# WIFI_Bluetooth.net
KiCad netlist of a schematic drawn in Altium Designer
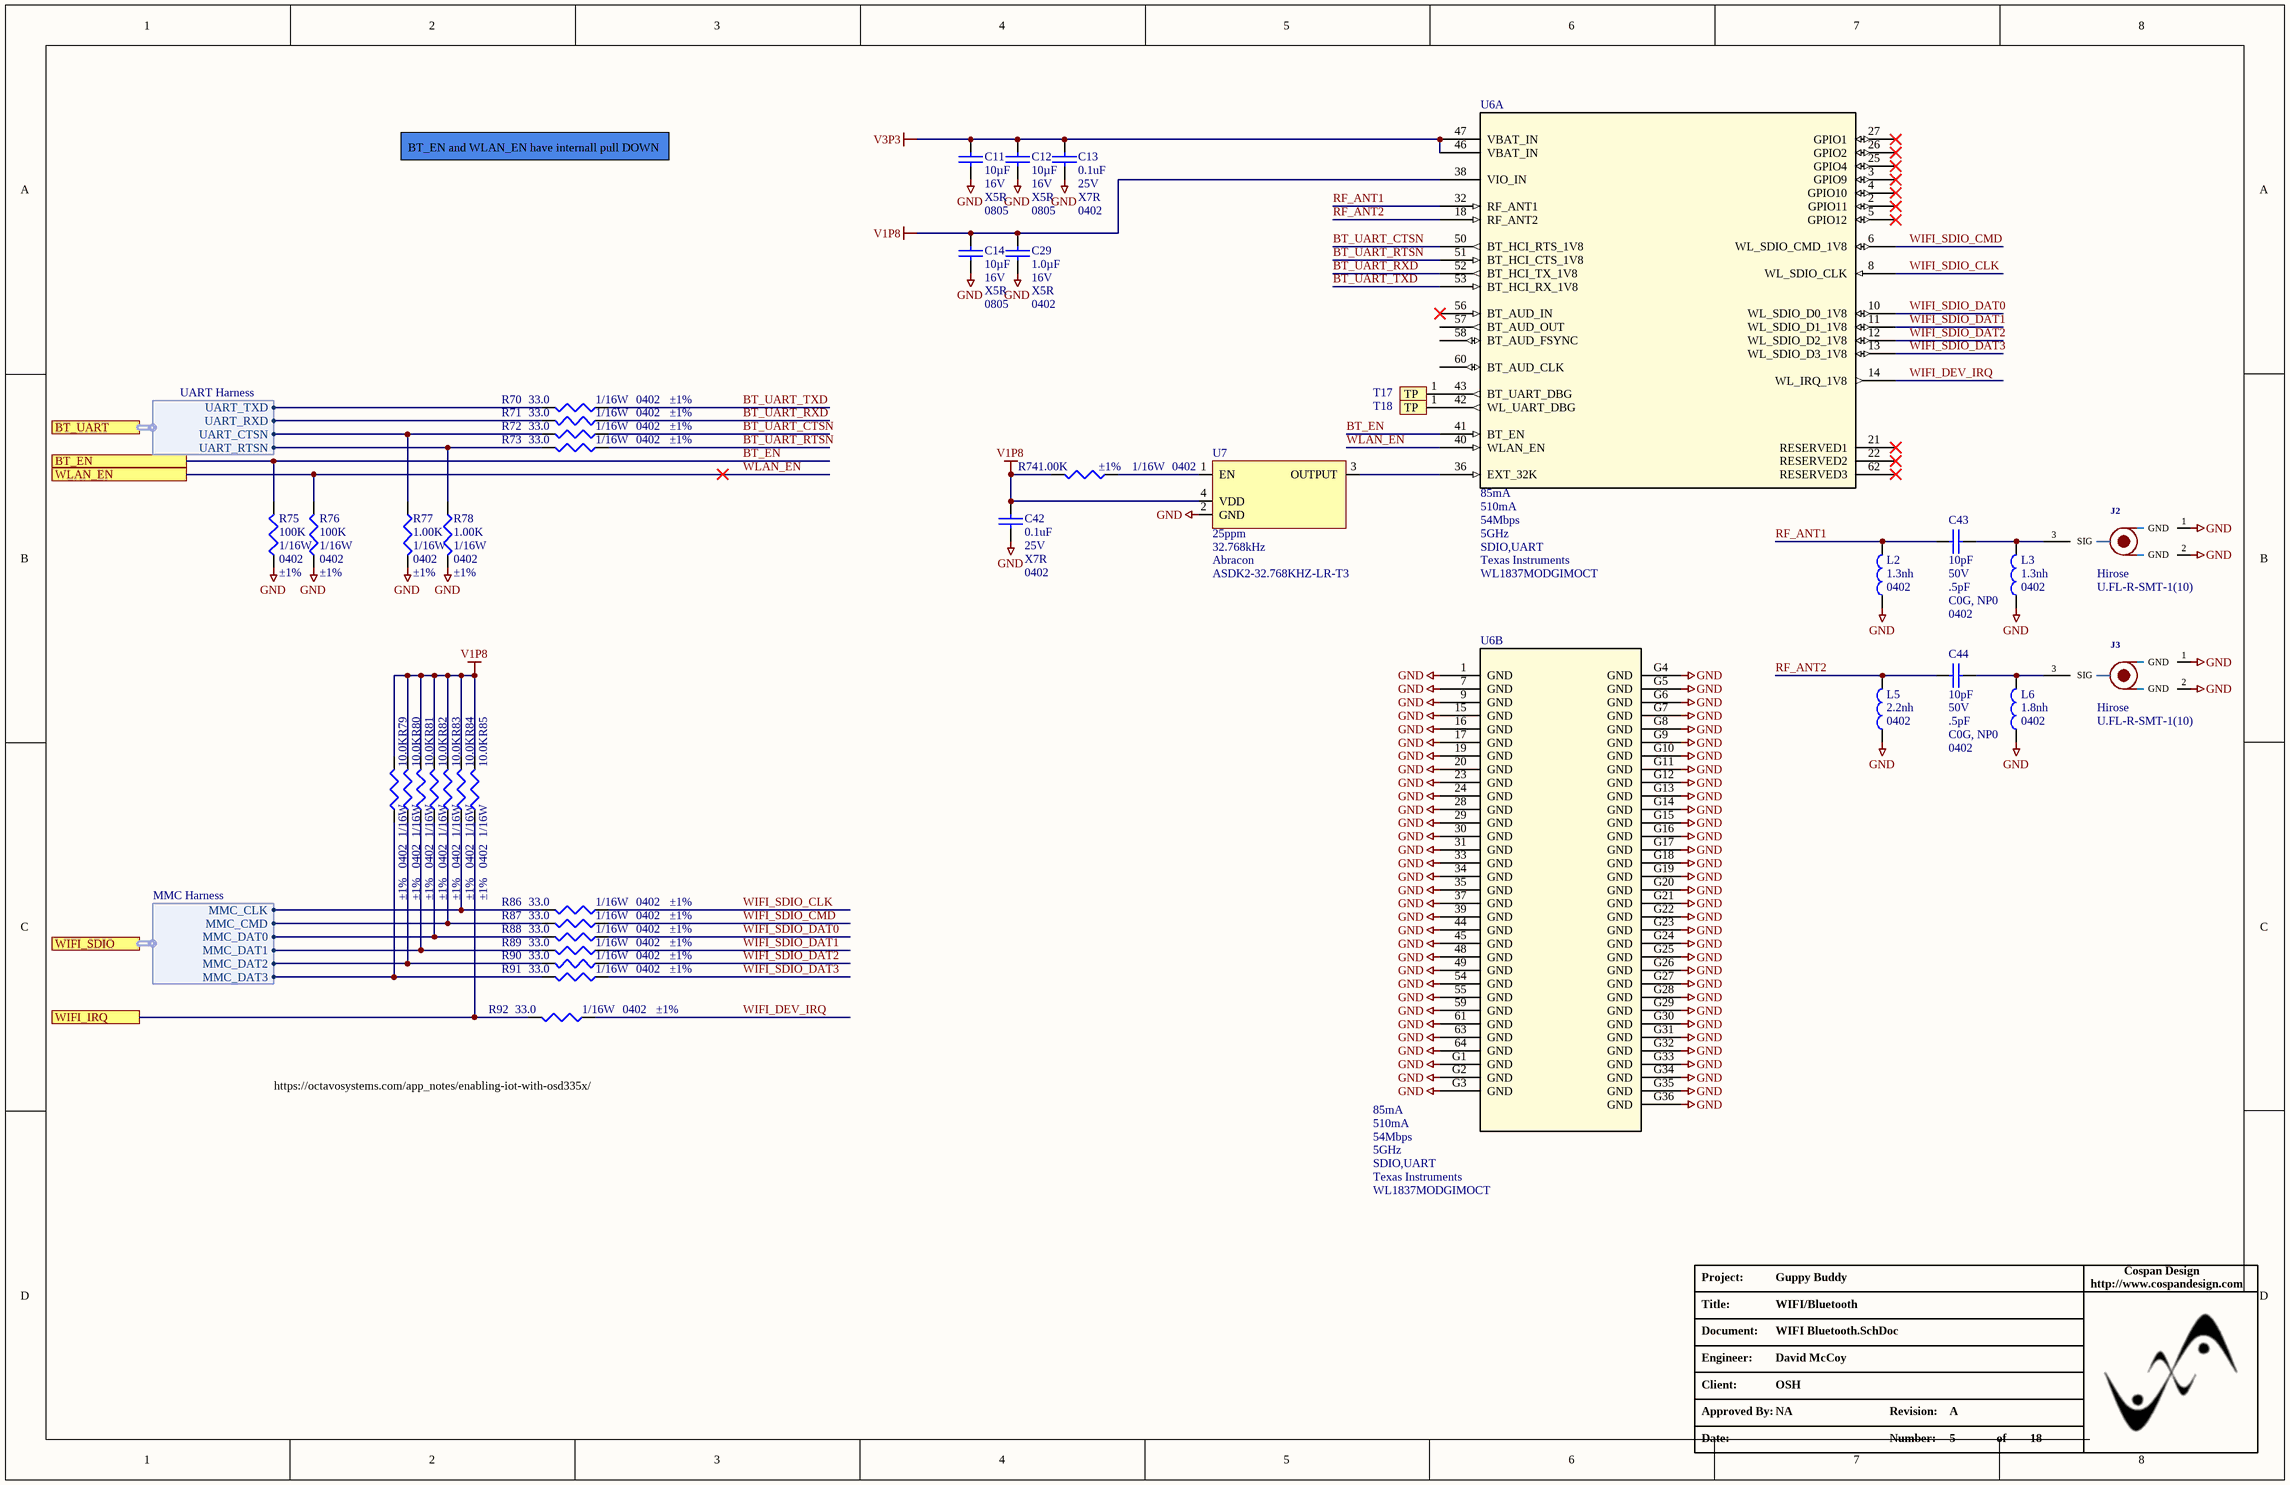
[diagram p0: WIFI Bluetooth.SchDoc]

(export (version "E")
  (design (tool "Eeschema 10.0.6"))
  (components
    (comp (ref "C11")
      (value "10µF")
      (footprint "C_ERA-0805")
      (description "CAP CER 10uF 16V X5R 20% 0805")
      (fields
        (field (name "MANUFACTURER") "Taiyo Yuden")
        (field (name "MANUFACTURER PART NUMBER") "EMK212BJ106KG-T")
        (field (name "CAPACITANCE") "10µF")
        (field (name "VOLTAGE - RATED") "16V")
        (field (name "TEMPERATURE COEFFICIENT") "X5R")
        (field (name "PACKAGE / CASE") "0805")
      )
      (libsource (lib "Main Library") (part "C_0805_10UF_16V"))
    )
    (comp (ref "C12")
      (value "10µF")
      (footprint "C_ERA-0805")
      (description "CAP CER 10uF 16V X5R 20% 0805")
      (fields
        (field (name "MANUFACTURER") "Taiyo Yuden")
        (field (name "MANUFACTURER PART NUMBER") "EMK212BJ106KG-T")
        (field (name "CAPACITANCE") "10µF")
        (field (name "VOLTAGE - RATED") "16V")
        (field (name "TEMPERATURE COEFFICIENT") "X5R")
        (field (name "PACKAGE / CASE") "0805")
      )
      (libsource (lib "Main Library") (part "C_0805_10UF_16V"))
    )
    (comp (ref "C13")
      (value "C_0402_0.1UF_25V")
      (footprint "C_0402")
      (description "CAP CER 0.1UF 25V X6S 0402")
      (fields
        (field (name "TOLERANCE") "10%")
        (field (name "CAPACITANCE") "0.1uF")
        (field (name "VOLTAGE - RATED") "25V")
        (field (name "TEMPERATURE COEFFICIENT") "X7R")
        (field (name "PACKAGE / CASE") "0402")
      )
      (libsource (lib "Cospan Design") (part "C_0402_0.1UF_25V"))
    )
    (comp (ref "C14")
      (value "10µF")
      (footprint "C_ERA-0805")
      (description "CAP CER 10uF 16V X5R 20% 0805")
      (fields
        (field (name "MANUFACTURER") "Taiyo Yuden")
        (field (name "MANUFACTURER PART NUMBER") "EMK212BJ106KG-T")
        (field (name "CAPACITANCE") "10µF")
        (field (name "VOLTAGE - RATED") "16V")
        (field (name "TEMPERATURE COEFFICIENT") "X5R")
        (field (name "PACKAGE / CASE") "0805")
      )
      (libsource (lib "Main Library") (part "C_0805_10UF_16V"))
    )
    (comp (ref "C29")
      (value "1.0uF")
      (footprint "C_0402")
      (description "CAP CER 1.0UF 16V X5R 0402")
      (fields
        (field (name "TOLERANCE") "10%")
        (field (name "CAPACITANCE") "1.0µF")
        (field (name "VOLTAGE - RATED") "16V")
        (field (name "TEMPERATURE COEFFICIENT") "X5R")
        (field (name "PACKAGE / CASE") "0402")
        (field (name "VOLTAGE") "16V")
      )
      (libsource (lib "Main LibraryX") (part "C_0402_1.0UF_16V"))
    )
    (comp (ref "C42")
      (value "C_0402_0.1UF_25V")
      (footprint "C_0402")
      (description "CAP CER 0.1UF 25V X6S 0402")
      (fields
        (field (name "TOLERANCE") "10%")
        (field (name "CAPACITANCE") "0.1uF")
        (field (name "VOLTAGE - RATED") "25V")
        (field (name "TEMPERATURE COEFFICIENT") "X7R")
        (field (name "PACKAGE / CASE") "0402")
      )
      (libsource (lib "Cospan Design") (part "C_0402_0.1UF_25V"))
    )
    (comp (ref "C43")
      (value "10pF")
      (footprint "C_0402")
      (description "CAP CER 10PF 50V NP0 0402")
      (fields
        (field (name "MANUFACTURER") "Taiyo Yuden")
        (field (name "MANUFACTURER PART NUMBER") "UMK105CG100DV-F")
        (field (name "CAPACITANCE") "10pF")
        (field (name "VOLTAGE - RATED") "50V")
        (field (name "TOLERANCE") ".5pF")
        (field (name "TEMPERATURE COEFFICIENT") "C0G, NP0")
        (field (name "PACKAGE / CASE") "0402")
      )
      (libsource (lib "Main Library") (part "C_0402_10PF_50V"))
    )
    (comp (ref "C44")
      (value "10pF")
      (footprint "C_0402")
      (description "CAP CER 10PF 50V NP0 0402")
      (fields
        (field (name "MANUFACTURER") "Taiyo Yuden")
        (field (name "MANUFACTURER PART NUMBER") "UMK105CG100DV-F")
        (field (name "CAPACITANCE") "10pF")
        (field (name "VOLTAGE - RATED") "50V")
        (field (name "TOLERANCE") ".5pF")
        (field (name "TEMPERATURE COEFFICIENT") "C0G, NP0")
        (field (name "PACKAGE / CASE") "0402")
      )
      (libsource (lib "Main Library") (part "C_0402_10PF_50V"))
    )
    (comp (ref "J2")
      (value "U.FL-R-SMT-1(10)")
      (footprint "U.FL-R-SMT-1")
      (description "CONN UMC JACK STR 50 OHM SMD")
      (fields
        (field (name "MANUFACTURER 1") "Hirose")
        (field (name "MANUFACTURER PART NUMBER 1") "U.FL-R-SMT-1(10)")
        (field (name "LIBRARYNAME") "GHI-Connectors")
      )
      (libsource (lib "Cospan Design") (part "J_U.FL-R-SMT-1"))
    )
    (comp (ref "J3")
      (value "U.FL-R-SMT-1(10)")
      (footprint "U.FL-R-SMT-1")
      (description "CONN UMC JACK STR 50 OHM SMD")
      (fields
        (field (name "MANUFACTURER 1") "Hirose")
        (field (name "MANUFACTURER PART NUMBER 1") "U.FL-R-SMT-1(10)")
        (field (name "LIBRARYNAME") "GHI-Connectors")
      )
      (libsource (lib "Cospan Design") (part "J_U.FL-R-SMT-1"))
    )
    (comp (ref "L2")
      (value "L_0402_1.3nH")
      (footprint "R_0402")
      (description "FIXED IND 1.3NH 1A 90 MOHM")
      (fields
        (field (name "TOLERANCE") "5%")
        (field (name "INDUCTANCE") "1.3nh")
        (field (name "CASE CODE (IMPERIAL)") "0402")
      )
      (libsource (lib "Cospan Design") (part "L_0402_1.3nH"))
    )
    (comp (ref "L3")
      (value "L_0402_1.3nH")
      (footprint "R_0402")
      (description "FIXED IND 1.3NH 1A 90 MOHM")
      (fields
        (field (name "TOLERANCE") "5%")
        (field (name "INDUCTANCE") "1.3nh")
        (field (name "CASE CODE (IMPERIAL)") "0402")
      )
      (libsource (lib "Cospan Design") (part "L_0402_1.3nH"))
    )
    (comp (ref "L5")
      (value "L_0402_2.2nH")
      (footprint "R_0402")
      (description "FIXED IND 2.2NH 950MA 150 MOHM")
      (fields (field (name "INDUCTANCE") "2.2nh") (field (name "CASE CODE (IMPERIAL)") "0402"))
      (libsource (lib "Cospan Design") (part "L_0402_2.2nH"))
    )
    (comp (ref "L6")
      (value "L_0402_1.8nH")
      (footprint "R_0402")
      (description "FIXED IND 1.8NH 950MA 100 MOHM")
      (fields (field (name "INDUCTANCE") "1.8nh") (field (name "CASE CODE (IMPERIAL)") "0402"))
      (libsource (lib "Cospan Design") (part "L_0402_1.8nH"))
    )
    (comp (ref "R70")
      (value "R_0402_33")
      (footprint "R_0402")
      (description "RES 33.0 OHM 1/16W 1% 0402 SMD")
      (fields
        (field (name "MANUFACTURER") "Yageo")
        (field (name "MANUFACTURER PART NUMBER") "RC0402FR-0733RL")
        (field (name "RESISTANCE IN OHMS") "33.0")
        (field (name "POWER (WATTS)") "1/16W")
        (field (name "CASE") "0402")
        (field (name "TOLERANCE") "±1%")
      )
      (libsource (lib "Main Library") (part "R_0402_33"))
    )
    (comp (ref "R71")
      (value "R_0402_33")
      (footprint "R_0402")
      (description "RES 33.0 OHM 1/16W 1% 0402 SMD")
      (fields
        (field (name "MANUFACTURER") "Yageo")
        (field (name "MANUFACTURER PART NUMBER") "RC0402FR-0733RL")
        (field (name "RESISTANCE IN OHMS") "33.0")
        (field (name "POWER (WATTS)") "1/16W")
        (field (name "CASE") "0402")
        (field (name "TOLERANCE") "±1%")
      )
      (libsource (lib "Main Library") (part "R_0402_33"))
    )
    (comp (ref "R72")
      (value "R_0402_33")
      (footprint "R_0402")
      (description "RES 33.0 OHM 1/16W 1% 0402 SMD")
      (fields
        (field (name "MANUFACTURER") "Yageo")
        (field (name "MANUFACTURER PART NUMBER") "RC0402FR-0733RL")
        (field (name "RESISTANCE IN OHMS") "33.0")
        (field (name "POWER (WATTS)") "1/16W")
        (field (name "CASE") "0402")
        (field (name "TOLERANCE") "±1%")
      )
      (libsource (lib "Main Library") (part "R_0402_33"))
    )
    (comp (ref "R73")
      (value "R_0402_33")
      (footprint "R_0402")
      (description "RES 33.0 OHM 1/16W 1% 0402 SMD")
      (fields
        (field (name "MANUFACTURER") "Yageo")
        (field (name "MANUFACTURER PART NUMBER") "RC0402FR-0733RL")
        (field (name "RESISTANCE IN OHMS") "33.0")
        (field (name "POWER (WATTS)") "1/16W")
        (field (name "CASE") "0402")
        (field (name "TOLERANCE") "±1%")
      )
      (libsource (lib "Main Library") (part "R_0402_33"))
    )
    (comp (ref "R74")
      (value "1.0k Ohms")
      (footprint "R_0402")
      (description "RES 1.00K OHM 1/16W 1% 0402 SMD")
      (fields
        (field (name "MANUFACTURER") "Yageo")
        (field (name "MANUFACTURER PART NUMBER") "RC0402FR-071KL")
        (field (name "RESISTANCE IN OHMS") "1.00K")
        (field (name "POWER (WATTS)") "1/16W")
        (field (name "CASE") "0402")
        (field (name "TOLERANCE") "±1%")
      )
      (libsource (lib "Main Library") (part "R_0402_1.0K"))
    )
    (comp (ref "R75")
      (value "R_0402_100.0K")
      (footprint "R_0402")
      (description "RES 100K OHM 1/16W 1% 0402 SMD")
      (fields
        (field (name "MANUFACTURER") "Stackpole Electronics Inc")
        (field (name "MANUFACTURER PART NUMBER") "RMCF0402FT100K")
        (field (name "RESISTANCE IN OHMS") "100K")
        (field (name "POWER (WATTS)") "1/16W")
        (field (name "CASE") "0402")
        (field (name "TOLERANCE") "±1%")
      )
      (libsource (lib "Main Library") (part "R_0402_100.0K"))
    )
    (comp (ref "R76")
      (value "R_0402_100.0K")
      (footprint "R_0402")
      (description "RES 100K OHM 1/16W 1% 0402 SMD")
      (fields
        (field (name "MANUFACTURER") "Stackpole Electronics Inc")
        (field (name "MANUFACTURER PART NUMBER") "RMCF0402FT100K")
        (field (name "RESISTANCE IN OHMS") "100K")
        (field (name "POWER (WATTS)") "1/16W")
        (field (name "CASE") "0402")
        (field (name "TOLERANCE") "±1%")
      )
      (libsource (lib "Main Library") (part "R_0402_100.0K"))
    )
    (comp (ref "R77")
      (value "1.0k Ohms")
      (footprint "R_0402")
      (description "RES 1.00K OHM 1/16W 1% 0402 SMD")
      (fields
        (field (name "MANUFACTURER") "Yageo")
        (field (name "MANUFACTURER PART NUMBER") "RC0402FR-071KL")
        (field (name "RESISTANCE IN OHMS") "1.00K")
        (field (name "POWER (WATTS)") "1/16W")
        (field (name "CASE") "0402")
        (field (name "TOLERANCE") "±1%")
      )
      (libsource (lib "Main Library") (part "R_0402_1.0K"))
    )
    (comp (ref "R78")
      (value "1.0k Ohms")
      (footprint "R_0402")
      (description "RES 1.00K OHM 1/16W 1% 0402 SMD")
      (fields
        (field (name "MANUFACTURER") "Yageo")
        (field (name "MANUFACTURER PART NUMBER") "RC0402FR-071KL")
        (field (name "RESISTANCE IN OHMS") "1.00K")
        (field (name "POWER (WATTS)") "1/16W")
        (field (name "CASE") "0402")
        (field (name "TOLERANCE") "±1%")
      )
      (libsource (lib "Main Library") (part "R_0402_1.0K"))
    )
    (comp (ref "R79")
      (value "R_0402_10.0K")
      (footprint "R_0402")
      (description "RES 10.0K OHM 1/16W 1% 0402 SMD")
      (fields
        (field (name "MANUFACTURER") "Stackpole Electronics Inc")
        (field (name "MANUFACTURER PART NUMBER") "RMCF0402FT10K0")
        (field (name "RESISTANCE IN OHMS") "10.0K")
        (field (name "POWER (WATTS)") "1/16W")
        (field (name "CASE") "0402")
        (field (name "TOLERANCE") "±1%")
      )
      (libsource (lib "Cospan Design") (part "R_0402_10.0K"))
    )
    (comp (ref "R80")
      (value "R_0402_10.0K")
      (footprint "R_0402")
      (description "RES 10.0K OHM 1/16W 1% 0402 SMD")
      (fields
        (field (name "MANUFACTURER") "Stackpole Electronics Inc")
        (field (name "MANUFACTURER PART NUMBER") "RMCF0402FT10K0")
        (field (name "RESISTANCE IN OHMS") "10.0K")
        (field (name "POWER (WATTS)") "1/16W")
        (field (name "CASE") "0402")
        (field (name "TOLERANCE") "±1%")
      )
      (libsource (lib "Cospan Design") (part "R_0402_10.0K"))
    )
    (comp (ref "R81")
      (value "R_0402_10.0K")
      (footprint "R_0402")
      (description "RES 10.0K OHM 1/16W 1% 0402 SMD")
      (fields
        (field (name "MANUFACTURER") "Stackpole Electronics Inc")
        (field (name "MANUFACTURER PART NUMBER") "RMCF0402FT10K0")
        (field (name "RESISTANCE IN OHMS") "10.0K")
        (field (name "POWER (WATTS)") "1/16W")
        (field (name "CASE") "0402")
        (field (name "TOLERANCE") "±1%")
      )
      (libsource (lib "Cospan Design") (part "R_0402_10.0K"))
    )
    (comp (ref "R82")
      (value "R_0402_10.0K")
      (footprint "R_0402")
      (description "RES 10.0K OHM 1/16W 1% 0402 SMD")
      (fields
        (field (name "MANUFACTURER") "Stackpole Electronics Inc")
        (field (name "MANUFACTURER PART NUMBER") "RMCF0402FT10K0")
        (field (name "RESISTANCE IN OHMS") "10.0K")
        (field (name "POWER (WATTS)") "1/16W")
        (field (name "CASE") "0402")
        (field (name "TOLERANCE") "±1%")
      )
      (libsource (lib "Cospan Design") (part "R_0402_10.0K"))
    )
    (comp (ref "R83")
      (value "R_0402_10.0K")
      (footprint "R_0402")
      (description "RES 10.0K OHM 1/16W 1% 0402 SMD")
      (fields
        (field (name "MANUFACTURER") "Stackpole Electronics Inc")
        (field (name "MANUFACTURER PART NUMBER") "RMCF0402FT10K0")
        (field (name "RESISTANCE IN OHMS") "10.0K")
        (field (name "POWER (WATTS)") "1/16W")
        (field (name "CASE") "0402")
        (field (name "TOLERANCE") "±1%")
      )
      (libsource (lib "Cospan Design") (part "R_0402_10.0K"))
    )
    (comp (ref "R84")
      (value "R_0402_10.0K")
      (footprint "R_0402")
      (description "RES 10.0K OHM 1/16W 1% 0402 SMD")
      (fields
        (field (name "MANUFACTURER") "Stackpole Electronics Inc")
        (field (name "MANUFACTURER PART NUMBER") "RMCF0402FT10K0")
        (field (name "RESISTANCE IN OHMS") "10.0K")
        (field (name "POWER (WATTS)") "1/16W")
        (field (name "CASE") "0402")
        (field (name "TOLERANCE") "±1%")
      )
      (libsource (lib "Cospan Design") (part "R_0402_10.0K"))
    )
    (comp (ref "R85")
      (value "R_0402_10.0K")
      (footprint "R_0402")
      (description "RES 10.0K OHM 1/16W 1% 0402 SMD")
      (fields
        (field (name "MANUFACTURER") "Stackpole Electronics Inc")
        (field (name "MANUFACTURER PART NUMBER") "RMCF0402FT10K0")
        (field (name "RESISTANCE IN OHMS") "10.0K")
        (field (name "POWER (WATTS)") "1/16W")
        (field (name "CASE") "0402")
        (field (name "TOLERANCE") "±1%")
      )
      (libsource (lib "Cospan Design") (part "R_0402_10.0K"))
    )
    (comp (ref "R86")
      (value "R_0402_33")
      (footprint "R_0402")
      (description "RES 33.0 OHM 1/16W 1% 0402 SMD")
      (fields
        (field (name "MANUFACTURER") "Yageo")
        (field (name "MANUFACTURER PART NUMBER") "RC0402FR-0733RL")
        (field (name "RESISTANCE IN OHMS") "33.0")
        (field (name "POWER (WATTS)") "1/16W")
        (field (name "CASE") "0402")
        (field (name "TOLERANCE") "±1%")
      )
      (libsource (lib "Main Library") (part "R_0402_33"))
    )
    (comp (ref "R87")
      (value "R_0402_33")
      (footprint "R_0402")
      (description "RES 33.0 OHM 1/16W 1% 0402 SMD")
      (fields
        (field (name "MANUFACTURER") "Yageo")
        (field (name "MANUFACTURER PART NUMBER") "RC0402FR-0733RL")
        (field (name "RESISTANCE IN OHMS") "33.0")
        (field (name "POWER (WATTS)") "1/16W")
        (field (name "CASE") "0402")
        (field (name "TOLERANCE") "±1%")
      )
      (libsource (lib "Main Library") (part "R_0402_33"))
    )
    (comp (ref "R88")
      (value "R_0402_33")
      (footprint "R_0402")
      (description "RES 33.0 OHM 1/16W 1% 0402 SMD")
      (fields
        (field (name "MANUFACTURER") "Yageo")
        (field (name "MANUFACTURER PART NUMBER") "RC0402FR-0733RL")
        (field (name "RESISTANCE IN OHMS") "33.0")
        (field (name "POWER (WATTS)") "1/16W")
        (field (name "CASE") "0402")
        (field (name "TOLERANCE") "±1%")
      )
      (libsource (lib "Main Library") (part "R_0402_33"))
    )
    (comp (ref "R89")
      (value "R_0402_33")
      (footprint "R_0402")
      (description "RES 33.0 OHM 1/16W 1% 0402 SMD")
      (fields
        (field (name "MANUFACTURER") "Yageo")
        (field (name "MANUFACTURER PART NUMBER") "RC0402FR-0733RL")
        (field (name "RESISTANCE IN OHMS") "33.0")
        (field (name "POWER (WATTS)") "1/16W")
        (field (name "CASE") "0402")
        (field (name "TOLERANCE") "±1%")
      )
      (libsource (lib "Main Library") (part "R_0402_33"))
    )
    (comp (ref "R90")
      (value "R_0402_33")
      (footprint "R_0402")
      (description "RES 33.0 OHM 1/16W 1% 0402 SMD")
      (fields
        (field (name "MANUFACTURER") "Yageo")
        (field (name "MANUFACTURER PART NUMBER") "RC0402FR-0733RL")
        (field (name "RESISTANCE IN OHMS") "33.0")
        (field (name "POWER (WATTS)") "1/16W")
        (field (name "CASE") "0402")
        (field (name "TOLERANCE") "±1%")
      )
      (libsource (lib "Main Library") (part "R_0402_33"))
    )
    (comp (ref "R91")
      (value "R_0402_33")
      (footprint "R_0402")
      (description "RES 33.0 OHM 1/16W 1% 0402 SMD")
      (fields
        (field (name "MANUFACTURER") "Yageo")
        (field (name "MANUFACTURER PART NUMBER") "RC0402FR-0733RL")
        (field (name "RESISTANCE IN OHMS") "33.0")
        (field (name "POWER (WATTS)") "1/16W")
        (field (name "CASE") "0402")
        (field (name "TOLERANCE") "±1%")
      )
      (libsource (lib "Main Library") (part "R_0402_33"))
    )
    (comp (ref "R92")
      (value "R_0402_33")
      (footprint "R_0402")
      (description "RES 33.0 OHM 1/16W 1% 0402 SMD")
      (fields
        (field (name "MANUFACTURER") "Yageo")
        (field (name "MANUFACTURER PART NUMBER") "RC0402FR-0733RL")
        (field (name "RESISTANCE IN OHMS") "33.0")
        (field (name "POWER (WATTS)") "1/16W")
        (field (name "CASE") "0402")
        (field (name "TOLERANCE") "±1%")
      )
      (libsource (lib "Main Library") (part "R_0402_33"))
    )
    (comp (ref "T17")
      (value "TEST_POINT_SMALL")
      (footprint "TestPointSmall")
      (description "OSCILLOSCOPE TEST POINT")
      (libsource (lib "Main LibraryX") (part "TEST_POINT_SMALL"))
    )
    (comp (ref "T18")
      (value "TEST_POINT_SMALL")
      (footprint "TestPointSmall")
      (description "OSCILLOSCOPE TEST POINT")
      (libsource (lib "Main LibraryX") (part "TEST_POINT_SMALL"))
    )
    (comp (ref "U6")
      (value "U_WL1837MODGIMOCT")
      (footprint "MOC0100A")
      (description "WiLink Wi-Fi 2.4/5GHz MIMO BT/BLE")
      (fields
        (field (name "CURRENT - RECEIVING") "85mA")
        (field (name "CURRENT - TRANSMITTING") "510mA")
        (field (name "DATA RATE") "54Mbps")
        (field (name "FREQUENCY") "5GHz")
        (field (name "INTERFACE") "SDIO,UART")
        (field (name "MANUFACTURER 1") "Texas Instruments")
        (field (name "MANUFACTURER PART NUMBER 1") "WL1837MODGIMOCT")
      )
      (libsource (lib "Cospan Design") (part "U_WL1837MODGIMOCT"))
    )
    (comp (ref "U7")
      (value "U_ASDK2-32.768KHZ-LR-T3")
      (footprint "KC2520B")
      (description "32.768kHz CMOS XO (Standard) Oscillator Surface Mount 1.8V 1.5mA Enable/Disable")
      (fields
        (field (name "FREQUENCY STABILITY") "25ppm")
        (field (name "FREQUENCY") "32.768kHz")
        (field (name "MANUFACTURER 1") "Abracon")
        (field (name "MANUFACTURER PART NUMBER 1") "ASDK2-32.768KHZ-LR-T3")
      )
      (libsource (lib "Cospan Design") (part "U_ASDK2-32.768KHZ-LR-T3"))
    )
  )
  (nets
    (net (code "4") (name "/BT_EN") (class "Default")
      (node (ref "R75") (pin "1") (pinfunction "1_1") (pintype "passive"))
      (node (ref "U6") (pin "41") (pinfunction "BT_EN_41") (pintype "input"))
    )
    (net (code "5") (name "/BT_UART_CTSN") (class "Default")
      (node (ref "R72") (pin "2") (pinfunction "2_2") (pintype "passive"))
      (node (ref "U6") (pin "50") (pinfunction "BT_HCI_RTS_1V8_50") (pintype "output"))
    )
    (net (code "6") (name "/BT_UART_RTSN") (class "Default")
      (node (ref "R73") (pin "2") (pinfunction "2_2") (pintype "passive"))
      (node (ref "U6") (pin "51") (pinfunction "BT_HCI_CTS_1V8_51") (pintype "input"))
    )
    (net (code "7") (name "/BT_UART_RXD") (class "Default")
      (node (ref "R71") (pin "2") (pinfunction "2_2") (pintype "passive"))
      (node (ref "U6") (pin "52") (pinfunction "BT_HCI_TX_1V8_52") (pintype "output"))
    )
    (net (code "8") (name "/BT_UART_TXD") (class "Default")
      (node (ref "R70") (pin "2") (pinfunction "2_2") (pintype "passive"))
      (node (ref "U6") (pin "53") (pinfunction "BT_HCI_RX_1V8_53") (pintype "input"))
    )
    (net (code "9") (name "/MMC_CLK") (class "Default")
      (node (ref "R84") (pin "2") (pinfunction "2_2") (pintype "passive"))
      (node (ref "R86") (pin "1") (pinfunction "1_1") (pintype "passive"))
    )
    (net (code "10") (name "/MMC_CMD") (class "Default")
      (node (ref "R83") (pin "2") (pinfunction "2_2") (pintype "passive"))
      (node (ref "R87") (pin "1") (pinfunction "1_1") (pintype "passive"))
    )
    (net (code "11") (name "/MMC_DAT0") (class "Default")
      (node (ref "R82") (pin "2") (pinfunction "2_2") (pintype "passive"))
      (node (ref "R88") (pin "1") (pinfunction "1_1") (pintype "passive"))
    )
    (net (code "12") (name "/MMC_DAT1") (class "Default")
      (node (ref "R81") (pin "2") (pinfunction "2_2") (pintype "passive"))
      (node (ref "R89") (pin "1") (pinfunction "1_1") (pintype "passive"))
    )
    (net (code "13") (name "/MMC_DAT2") (class "Default")
      (node (ref "R80") (pin "2") (pinfunction "2_2") (pintype "passive"))
      (node (ref "R90") (pin "1") (pinfunction "1_1") (pintype "passive"))
    )
    (net (code "14") (name "/MMC_DAT3") (class "Default")
      (node (ref "R79") (pin "2") (pinfunction "2_2") (pintype "passive"))
      (node (ref "R91") (pin "1") (pinfunction "1_1") (pintype "passive"))
    )
    (net (code "15") (name "/RF_ANT1") (class "Default")
      (node (ref "C43") (pin "2") (pinfunction "2_2") (pintype "passive"))
      (node (ref "L2") (pin "2") (pintype "passive"))
      (node (ref "U6") (pin "32") (pinfunction "RF_ANT1_32") (pintype "input"))
    )
    (net (code "16") (name "/RF_ANT2") (class "Default")
      (node (ref "C44") (pin "2") (pinfunction "2_2") (pintype "passive"))
      (node (ref "L5") (pin "2") (pintype "passive"))
      (node (ref "U6") (pin "18") (pinfunction "RF_ANT2_18") (pintype "input"))
    )
    (net (code "17") (name "/UART_CTSN") (class "Default")
      (node (ref "R72") (pin "1") (pinfunction "1_1") (pintype "passive"))
      (node (ref "R77") (pin "2") (pinfunction "2_2") (pintype "passive"))
    )
    (net (code "18") (name "/UART_RTSN") (class "Default")
      (node (ref "R73") (pin "1") (pinfunction "1_1") (pintype "passive"))
      (node (ref "R78") (pin "2") (pinfunction "2_2") (pintype "passive"))
    )
    (net (code "19") (name "/UART_RXD") (class "Default")
      (node (ref "R71") (pin "1") (pinfunction "1_1") (pintype "passive"))
    )
    (net (code "20") (name "/UART_TXD") (class "Default")
      (node (ref "R70") (pin "1") (pinfunction "1_1") (pintype "passive"))
    )
    (net (code "21") (name "/WIFI_DEV_IRQ") (class "Default")
      (node (ref "R92") (pin "2") (pinfunction "2_2") (pintype "passive"))
      (node (ref "U6") (pin "14") (pinfunction "WL_IRQ_1V8_14") (pintype "output"))
    )
    (net (code "22") (name "/WIFI_IRQ") (class "Default")
      (node (ref "R85") (pin "2") (pinfunction "2_2") (pintype "passive"))
      (node (ref "R92") (pin "1") (pinfunction "1_1") (pintype "passive"))
    )
    (net (code "23") (name "/WIFI_SDIO_CLK") (class "Default")
      (node (ref "R86") (pin "2") (pinfunction "2_2") (pintype "passive"))
      (node (ref "U6") (pin "8") (pinfunction "WL_SDIO_CLK_8") (pintype "input"))
    )
    (net (code "24") (name "/WIFI_SDIO_CMD") (class "Default")
      (node (ref "R87") (pin "2") (pinfunction "2_2") (pintype "passive"))
      (node (ref "U6") (pin "6") (pinfunction "WL_SDIO_CMD_1V8_6") (pintype "bidirectional"))
    )
    (net (code "25") (name "/WIFI_SDIO_DAT0") (class "Default")
      (node (ref "R88") (pin "2") (pinfunction "2_2") (pintype "passive"))
      (node (ref "U6") (pin "10") (pinfunction "WL_SDIO_D0_1V8_10") (pintype "bidirectional"))
    )
    (net (code "26") (name "/WIFI_SDIO_DAT1") (class "Default")
      (node (ref "R89") (pin "2") (pinfunction "2_2") (pintype "passive"))
      (node (ref "U6") (pin "11") (pinfunction "WL_SDIO_D1_1V8_11") (pintype "bidirectional"))
    )
    (net (code "27") (name "/WIFI_SDIO_DAT2") (class "Default")
      (node (ref "R90") (pin "2") (pinfunction "2_2") (pintype "passive"))
      (node (ref "U6") (pin "12") (pinfunction "WL_SDIO_D2_1V8_12") (pintype "bidirectional"))
    )
    (net (code "28") (name "/WIFI_SDIO_DAT3") (class "Default")
      (node (ref "R91") (pin "2") (pinfunction "2_2") (pintype "passive"))
      (node (ref "U6") (pin "13") (pinfunction "WL_SDIO_D3_1V8_13") (pintype "bidirectional"))
    )
    (net (code "29") (name "/WLAN_EN") (class "Default")
      (node (ref "R76") (pin "1") (pinfunction "1_1") (pintype "passive"))
      (node (ref "U6") (pin "40") (pinfunction "WLAN_EN_40") (pintype "input"))
    )
    (net (code "32") (name "GND") (class "Default")
      (node (ref "C11") (pin "1") (pinfunction "1_1") (pintype "passive"))
      (node (ref "C12") (pin "1") (pinfunction "1_1") (pintype "passive"))
      (node (ref "C13") (pin "1") (pinfunction "1_1") (pintype "passive"))
      (node (ref "C14") (pin "1") (pinfunction "1_1") (pintype "passive"))
      (node (ref "C29") (pin "1") (pinfunction "1_1") (pintype "passive"))
      (node (ref "C42") (pin "1") (pinfunction "1_1") (pintype "passive"))
      (node (ref "J2") (pin "1") (pinfunction "GND_1") (pintype "passive"))
      (node (ref "J2") (pin "2") (pinfunction "GND_2") (pintype "passive"))
      (node (ref "J3") (pin "1") (pinfunction "GND_1") (pintype "passive"))
      (node (ref "J3") (pin "2") (pinfunction "GND_2") (pintype "passive"))
      (node (ref "L2") (pin "1") (pintype "passive"))
      (node (ref "L3") (pin "1") (pintype "passive"))
      (node (ref "L5") (pin "1") (pintype "passive"))
      (node (ref "L6") (pin "1") (pintype "passive"))
      (node (ref "R75") (pin "2") (pinfunction "2_2") (pintype "passive"))
      (node (ref "R76") (pin "2") (pinfunction "2_2") (pintype "passive"))
      (node (ref "R77") (pin "1") (pinfunction "1_1") (pintype "passive"))
      (node (ref "R78") (pin "1") (pinfunction "1_1") (pintype "passive"))
      (node (ref "U6") (pin "1") (pinfunction "GND_1") (pintype "power_in"))
      (node (ref "U6") (pin "15") (pinfunction "GND_15") (pintype "power_in"))
      (node (ref "U6") (pin "16") (pinfunction "GND_16") (pintype "power_in"))
      (node (ref "U6") (pin "17") (pinfunction "GND_17") (pintype "power_in"))
      (node (ref "U6") (pin "19") (pinfunction "GND_19") (pintype "power_in"))
      (node (ref "U6") (pin "20") (pinfunction "GND_20") (pintype "power_in"))
      (node (ref "U6") (pin "23") (pinfunction "GND_23") (pintype "power_in"))
      (node (ref "U6") (pin "24") (pinfunction "GND_24") (pintype "power_in"))
      (node (ref "U6") (pin "28") (pinfunction "GND_28") (pintype "power_in"))
      (node (ref "U6") (pin "29") (pinfunction "GND_29") (pintype "power_in"))
      (node (ref "U6") (pin "30") (pinfunction "GND_30") (pintype "power_in"))
      (node (ref "U6") (pin "31") (pinfunction "GND_31") (pintype "power_in"))
      (node (ref "U6") (pin "33") (pinfunction "GND_33") (pintype "power_in"))
      (node (ref "U6") (pin "34") (pinfunction "GND_34") (pintype "power_in"))
      (node (ref "U6") (pin "35") (pinfunction "GND_35") (pintype "power_in"))
      (node (ref "U6") (pin "37") (pinfunction "GND_37") (pintype "power_in"))
      (node (ref "U6") (pin "39") (pinfunction "GND_39") (pintype "power_in"))
      (node (ref "U6") (pin "44") (pinfunction "GND_44") (pintype "power_in"))
      (node (ref "U6") (pin "45") (pinfunction "GND_45") (pintype "power_in"))
      (node (ref "U6") (pin "48") (pinfunction "GND_48") (pintype "power_in"))
      (node (ref "U6") (pin "49") (pinfunction "GND_49") (pintype "power_in"))
      (node (ref "U6") (pin "54") (pinfunction "GND_54") (pintype "power_in"))
      (node (ref "U6") (pin "55") (pinfunction "GND_55") (pintype "power_in"))
      (node (ref "U6") (pin "59") (pinfunction "GND_59") (pintype "power_in"))
      (node (ref "U6") (pin "61") (pinfunction "GND_61") (pintype "power_in"))
      (node (ref "U6") (pin "63") (pinfunction "GND_63") (pintype "power_in"))
      (node (ref "U6") (pin "64") (pinfunction "GND_64") (pintype "power_in"))
      (node (ref "U6") (pin "7") (pinfunction "GND_7") (pintype "power_in"))
      (node (ref "U6") (pin "9") (pinfunction "GND_9") (pintype "power_in"))
      (node (ref "U6") (pin "G1") (pinfunction "GND_G1") (pintype "power_in"))
      (node (ref "U6") (pin "G10") (pinfunction "GND_G10") (pintype "power_in"))
      (node (ref "U6") (pin "G11") (pinfunction "GND_G11") (pintype "power_in"))
      (node (ref "U6") (pin "G12") (pinfunction "GND_G12") (pintype "power_in"))
      (node (ref "U6") (pin "G13") (pinfunction "GND_G13") (pintype "power_in"))
      (node (ref "U6") (pin "G14") (pinfunction "GND_G14") (pintype "power_in"))
      (node (ref "U6") (pin "G15") (pinfunction "GND_G15") (pintype "power_in"))
      (node (ref "U6") (pin "G16") (pinfunction "GND_G16") (pintype "power_in"))
      (node (ref "U6") (pin "G17") (pinfunction "GND_G17") (pintype "power_in"))
      (node (ref "U6") (pin "G18") (pinfunction "GND_G18") (pintype "power_in"))
      (node (ref "U6") (pin "G19") (pinfunction "GND_G19") (pintype "power_in"))
      (node (ref "U6") (pin "G2") (pinfunction "GND_G2") (pintype "power_in"))
      (node (ref "U6") (pin "G20") (pinfunction "GND_G20") (pintype "power_in"))
      (node (ref "U6") (pin "G21") (pinfunction "GND_G21") (pintype "power_in"))
      (node (ref "U6") (pin "G22") (pinfunction "GND_G22") (pintype "power_in"))
      (node (ref "U6") (pin "G23") (pinfunction "GND_G23") (pintype "power_in"))
      (node (ref "U6") (pin "G24") (pinfunction "GND_G24") (pintype "power_in"))
      (node (ref "U6") (pin "G25") (pinfunction "GND_G25") (pintype "power_in"))
      (node (ref "U6") (pin "G26") (pinfunction "GND_G26") (pintype "power_in"))
      (node (ref "U6") (pin "G27") (pinfunction "GND_G27") (pintype "power_in"))
      (node (ref "U6") (pin "G28") (pinfunction "GND_G28") (pintype "power_in"))
      (node (ref "U6") (pin "G29") (pinfunction "GND_G29") (pintype "power_in"))
      (node (ref "U6") (pin "G3") (pinfunction "GND_G3") (pintype "power_in"))
      (node (ref "U6") (pin "G30") (pinfunction "GND_G30") (pintype "power_in"))
      (node (ref "U6") (pin "G31") (pinfunction "GND_G31") (pintype "power_in"))
      (node (ref "U6") (pin "G32") (pinfunction "GND_G32") (pintype "power_in"))
      (node (ref "U6") (pin "G33") (pinfunction "GND_G33") (pintype "power_in"))
      (node (ref "U6") (pin "G34") (pinfunction "GND_G34") (pintype "power_in"))
      (node (ref "U6") (pin "G35") (pinfunction "GND_G35") (pintype "power_in"))
      (node (ref "U6") (pin "G36") (pinfunction "GND_G36") (pintype "power_in"))
      (node (ref "U6") (pin "G4") (pinfunction "GND_G4") (pintype "power_in"))
      (node (ref "U6") (pin "G5") (pinfunction "GND_G5") (pintype "power_in"))
      (node (ref "U6") (pin "G6") (pinfunction "GND_G6") (pintype "power_in"))
      (node (ref "U6") (pin "G7") (pinfunction "GND_G7") (pintype "power_in"))
      (node (ref "U6") (pin "G8") (pinfunction "GND_G8") (pintype "power_in"))
      (node (ref "U6") (pin "G9") (pinfunction "GND_G9") (pintype "power_in"))
      (node (ref "U7") (pin "2") (pinfunction "GND_2") (pintype "passive"))
    )
    (net (code "33") (name "Net-(J2-SIG)") (class "Default")
      (node (ref "C43") (pin "1") (pinfunction "1_1") (pintype "passive"))
      (node (ref "J2") (pin "3") (pinfunction "SIG_3") (pintype "passive"))
      (node (ref "L3") (pin "2") (pintype "passive"))
    )
    (net (code "34") (name "Net-(J3-SIG)") (class "Default")
      (node (ref "C44") (pin "1") (pinfunction "1_1") (pintype "passive"))
      (node (ref "J3") (pin "3") (pinfunction "SIG_3") (pintype "passive"))
      (node (ref "L6") (pin "2") (pintype "passive"))
    )
    (net (code "35") (name "Net-(T17-TP)") (class "Default")
      (node (ref "T17") (pin "1") (pinfunction "TP_1") (pintype "passive"))
      (node (ref "U6") (pin "43") (pinfunction "BT_UART_DBG_43") (pintype "output"))
    )
    (net (code "36") (name "Net-(T18-TP)") (class "Default")
      (node (ref "T18") (pin "1") (pinfunction "TP_1") (pintype "passive"))
      (node (ref "U6") (pin "42") (pinfunction "WL_UART_DBG_42") (pintype "output"))
    )
    (net (code "37") (name "Net-(U6A-EXT_32K)") (class "Default")
      (node (ref "U6") (pin "36") (pinfunction "EXT_32K_36") (pintype "input"))
      (node (ref "U7") (pin "3") (pinfunction "OUTPUT_3") (pintype "passive"))
    )
    (net (code "38") (name "Net-(U7-EN)") (class "Default")
      (node (ref "R74") (pin "2") (pinfunction "2_2") (pintype "passive"))
      (node (ref "U7") (pin "1") (pinfunction "EN_1") (pintype "passive"))
    )
    (net (code "39") (name "V1P8") (class "Default")
      (node (ref "C14") (pin "2") (pinfunction "2_2") (pintype "passive"))
      (node (ref "C29") (pin "2") (pinfunction "2_2") (pintype "passive"))
      (node (ref "C42") (pin "2") (pinfunction "2_2") (pintype "passive"))
      (node (ref "R74") (pin "1") (pinfunction "1_1") (pintype "passive"))
      (node (ref "R79") (pin "1") (pinfunction "1_1") (pintype "passive"))
      (node (ref "R80") (pin "1") (pinfunction "1_1") (pintype "passive"))
      (node (ref "R81") (pin "1") (pinfunction "1_1") (pintype "passive"))
      (node (ref "R82") (pin "1") (pinfunction "1_1") (pintype "passive"))
      (node (ref "R83") (pin "1") (pinfunction "1_1") (pintype "passive"))
      (node (ref "R84") (pin "1") (pinfunction "1_1") (pintype "passive"))
      (node (ref "R85") (pin "1") (pinfunction "1_1") (pintype "passive"))
      (node (ref "U6") (pin "38") (pinfunction "VIO_IN_38") (pintype "power_in"))
      (node (ref "U7") (pin "4") (pinfunction "VDD_4") (pintype "passive"))
    )
    (net (code "40") (name "V3P3") (class "Default")
      (node (ref "C11") (pin "2") (pinfunction "2_2") (pintype "passive"))
      (node (ref "C12") (pin "2") (pinfunction "2_2") (pintype "passive"))
      (node (ref "C13") (pin "2") (pinfunction "2_2") (pintype "passive"))
      (node (ref "U6") (pin "46") (pinfunction "VBAT_IN_46") (pintype "power_in"))
      (node (ref "U6") (pin "47") (pinfunction "VBAT_IN_47") (pintype "power_in"))
    )
    (net (code "41") (name "unconnected-(U6A-BT_AUD_CLK-Pad60)") (class "Default")
      (node (ref "U6") (pin "60") (pinfunction "BT_AUD_CLK_60") (pintype "bidirectional"))
    )
    (net (code "42") (name "unconnected-(U6A-BT_AUD_FSYNC-Pad58)") (class "Default")
      (node (ref "U6") (pin "58") (pinfunction "BT_AUD_FSYNC_58") (pintype "bidirectional"))
    )
    (net (code "43") (name "unconnected-(U6A-BT_AUD_IN-Pad56)") (class "Default")
      (node (ref "U6") (pin "56") (pinfunction "BT_AUD_IN_56") (pintype "input+no_connect"))
    )
    (net (code "44") (name "unconnected-(U6A-BT_AUD_OUT-Pad57)") (class "Default")
      (node (ref "U6") (pin "57") (pinfunction "BT_AUD_OUT_57") (pintype "output"))
    )
    (net (code "45") (name "unconnected-(U6A-GPIO1-Pad27)") (class "Default")
      (node (ref "U6") (pin "27") (pinfunction "GPIO1_27") (pintype "bidirectional+no_connect"))
    )
    (net (code "46") (name "unconnected-(U6A-GPIO2-Pad26)") (class "Default")
      (node (ref "U6") (pin "26") (pinfunction "GPIO2_26") (pintype "bidirectional+no_connect"))
    )
    (net (code "47") (name "unconnected-(U6A-GPIO4-Pad25)") (class "Default")
      (node (ref "U6") (pin "25") (pinfunction "GPIO4_25") (pintype "bidirectional+no_connect"))
    )
    (net (code "48") (name "unconnected-(U6A-GPIO9-Pad3)") (class "Default")
      (node (ref "U6") (pin "3") (pinfunction "GPIO9_3") (pintype "bidirectional+no_connect"))
    )
    (net (code "49") (name "unconnected-(U6A-GPIO10-Pad4)") (class "Default")
      (node (ref "U6") (pin "4") (pinfunction "GPIO10_4") (pintype "bidirectional+no_connect"))
    )
    (net (code "50") (name "unconnected-(U6A-GPIO11-Pad2)") (class "Default")
      (node (ref "U6") (pin "2") (pinfunction "GPIO11_2") (pintype "bidirectional+no_connect"))
    )
    (net (code "51") (name "unconnected-(U6A-GPIO12-Pad5)") (class "Default")
      (node (ref "U6") (pin "5") (pinfunction "GPIO12_5") (pintype "bidirectional+no_connect"))
    )
    (net (code "52") (name "unconnected-(U6A-RESERVED1-Pad21)") (class "Default")
      (node (ref "U6") (pin "21") (pinfunction "RESERVED1_21") (pintype "passive+no_connect"))
    )
    (net (code "53") (name "unconnected-(U6A-RESERVED2-Pad22)") (class "Default")
      (node (ref "U6") (pin "22") (pinfunction "RESERVED2_22") (pintype "passive+no_connect"))
    )
    (net (code "54") (name "unconnected-(U6A-RESERVED3-Pad62)") (class "Default")
      (node (ref "U6") (pin "62") (pinfunction "RESERVED3_62") (pintype "passive+no_connect"))
    )
  )
)
